# controller.net
KiCad netlist of a schematic drawn in Altium Designer
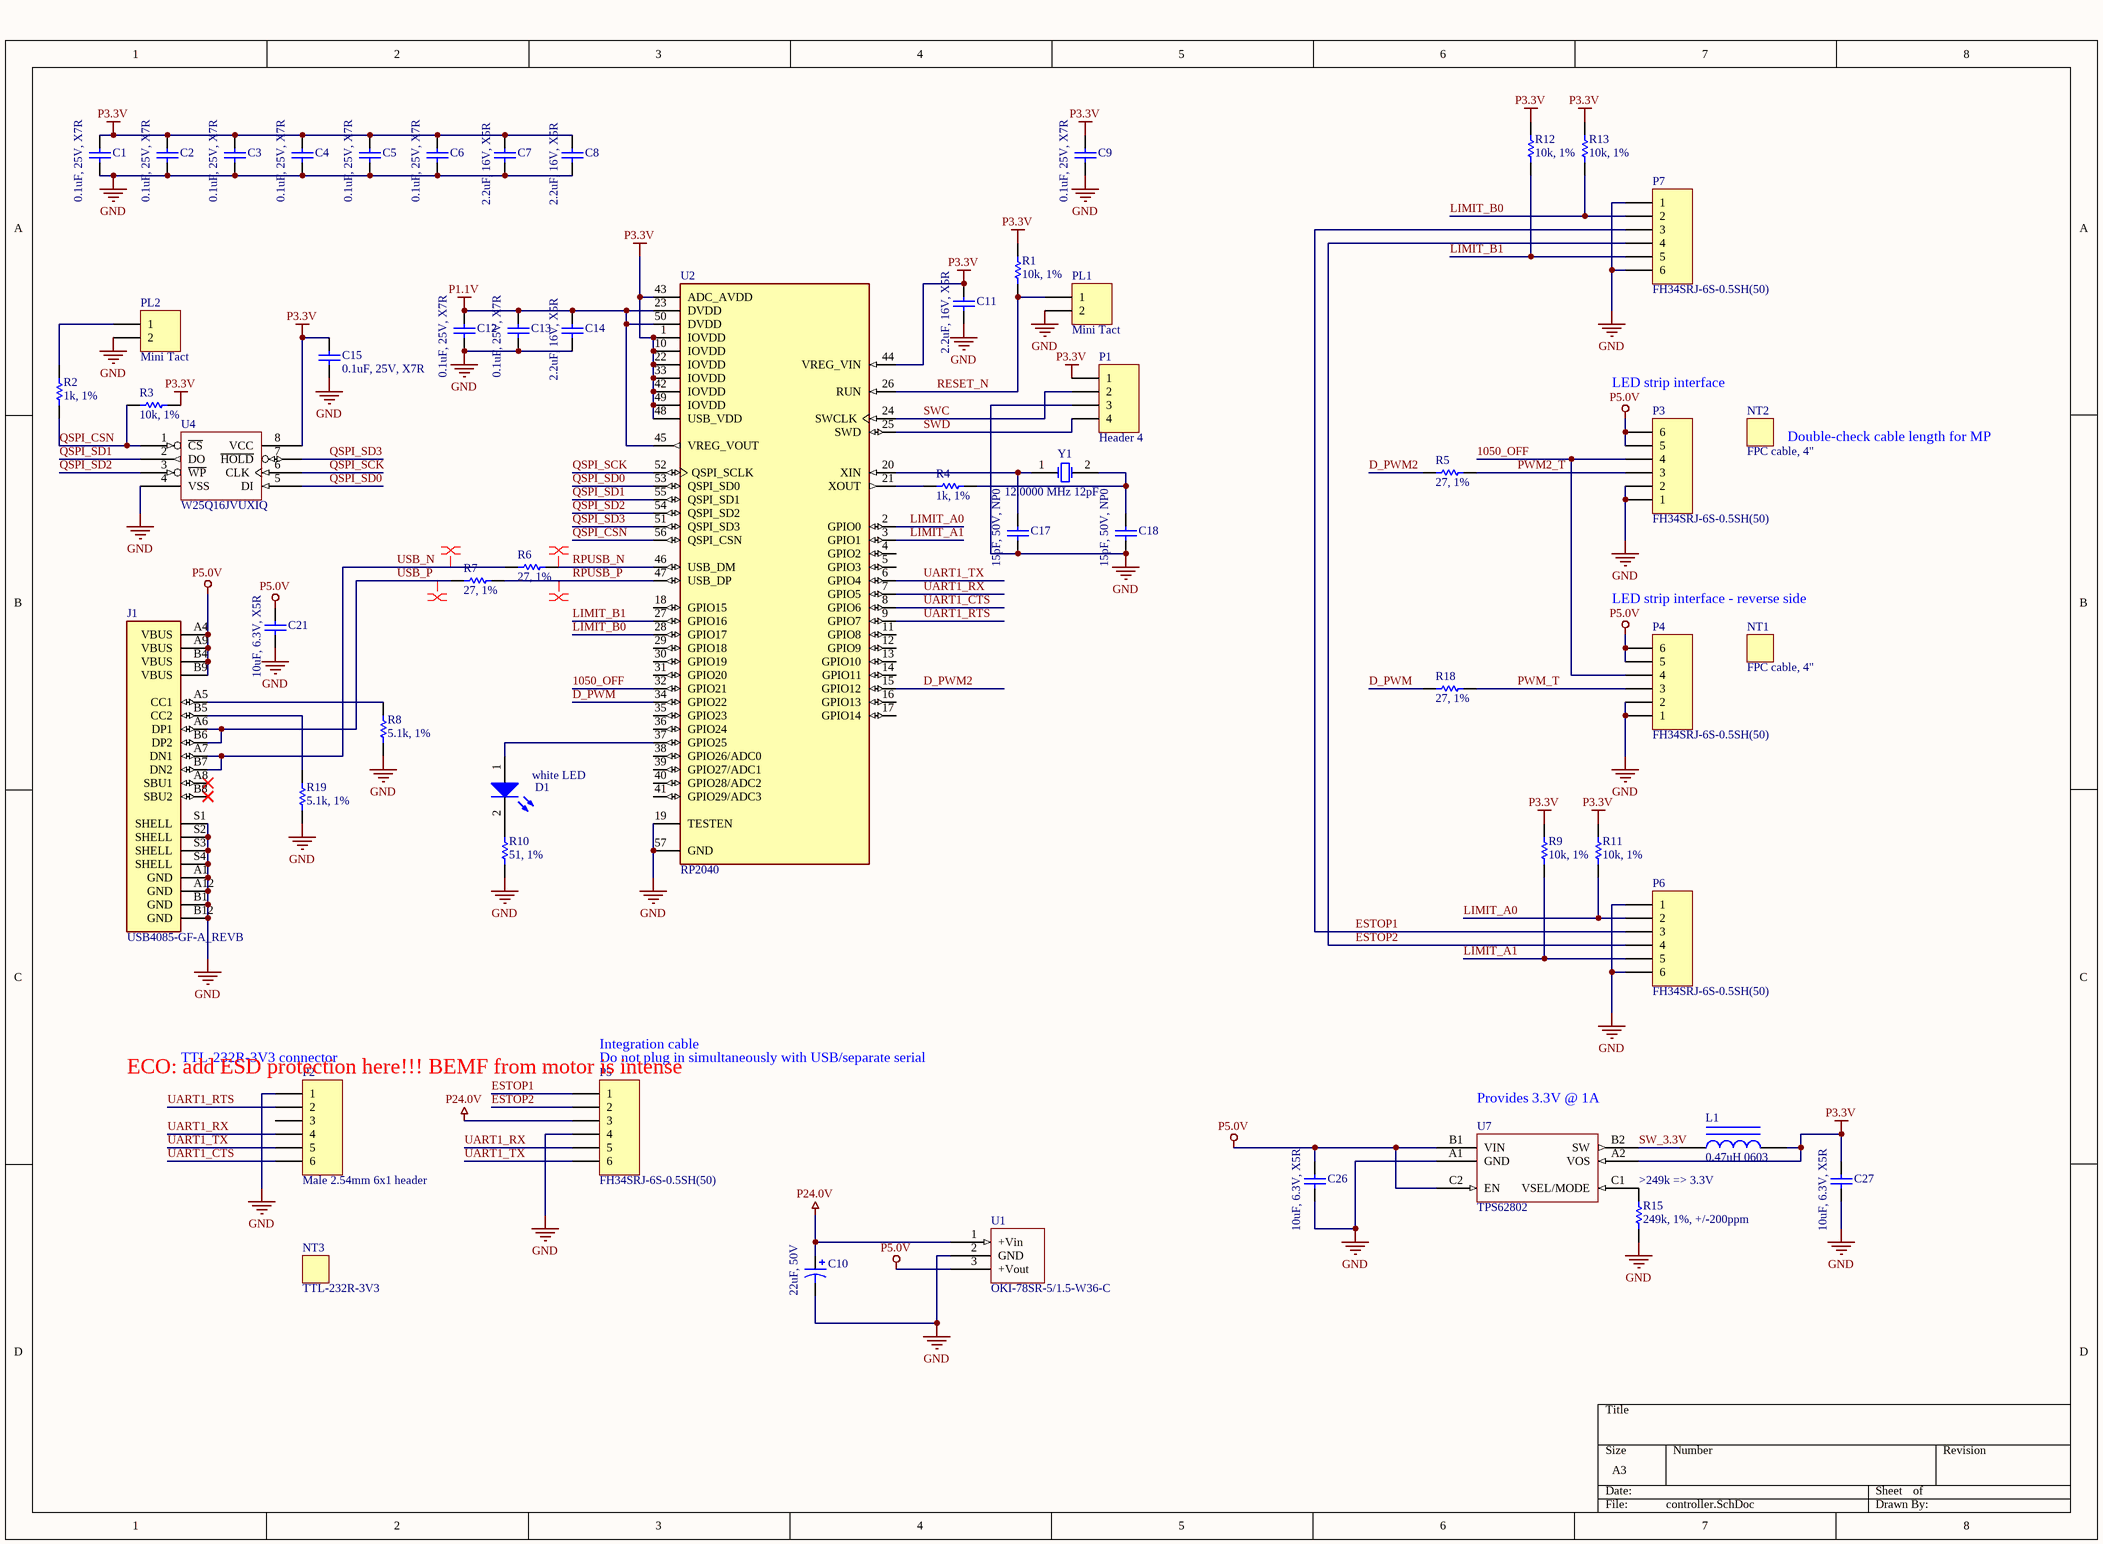
[diagram p0: controller.SchDoc]

(export (version "E")
  (design (tool "Eeschema 10.0.6"))
  (components
    (comp (ref "C1")
      (value "0.1uF, 25V, X7R")
      (footprint "B_CAP0603")
      (description "Capacitor (Semiconductor SIM Model)")
      (fields (field (name "MPN") "CC0603KRX7R8BB104"))
      (libsource (lib "Miscellaneous Devices") (part "Cap Semi"))
    )
    (comp (ref "C2")
      (value "0.1uF, 25V, X7R")
      (footprint "B_CAP0603")
      (description "Capacitor (Semiconductor SIM Model)")
      (fields (field (name "MPN") "CC0603KRX7R8BB104"))
      (libsource (lib "Miscellaneous Devices") (part "Cap Semi"))
    )
    (comp (ref "C3")
      (value "0.1uF, 25V, X7R")
      (footprint "B_CAP0603")
      (description "Capacitor (Semiconductor SIM Model)")
      (fields (field (name "MPN") "CC0603KRX7R8BB104"))
      (libsource (lib "Miscellaneous Devices") (part "Cap Semi"))
    )
    (comp (ref "C4")
      (value "0.1uF, 25V, X7R")
      (footprint "B_CAP0603")
      (description "Capacitor (Semiconductor SIM Model)")
      (fields (field (name "MPN") "CC0603KRX7R8BB104"))
      (libsource (lib "Miscellaneous Devices") (part "Cap Semi"))
    )
    (comp (ref "C5")
      (value "0.1uF, 25V, X7R")
      (footprint "B_CAP0603")
      (description "Capacitor (Semiconductor SIM Model)")
      (fields (field (name "MPN") "CC0603KRX7R8BB104"))
      (libsource (lib "Miscellaneous Devices") (part "Cap Semi"))
    )
    (comp (ref "C6")
      (value "0.1uF, 25V, X7R")
      (footprint "B_CAP0603")
      (description "Capacitor (Semiconductor SIM Model)")
      (fields (field (name "MPN") "CC0603KRX7R8BB104"))
      (libsource (lib "Miscellaneous Devices") (part "Cap Semi"))
    )
    (comp (ref "C7")
      (value "2.2uF, 16V, X5R")
      (footprint "B_CAP0603")
      (description "Capacitor (Semiconductor SIM Model)")
      (fields (field (name "MPN") "CL10A225KO8NNNC"))
      (libsource (lib "Miscellaneous Devices") (part "Cap Semi"))
    )
    (comp (ref "C8")
      (value "2.2uF, 16V, X5R")
      (footprint "B_CAP0603")
      (description "Capacitor (Semiconductor SIM Model)")
      (fields (field (name "MPN") "CL10A225KO8NNNC"))
      (libsource (lib "Miscellaneous Devices") (part "Cap Semi"))
    )
    (comp (ref "C9")
      (value "0.1uF, 25V, X7R")
      (footprint "B_CAP0603")
      (description "Capacitor (Semiconductor SIM Model)")
      (fields (field (name "MPN") "CC0603KRX7R8BB104"))
      (libsource (lib "Miscellaneous Devices") (part "Cap Semi"))
    )
    (comp (ref "C10")
      (value "22uF, 50V")
      (footprint "CAPAE7066X61N")
      (description "Polarized Capacitor (Radial)")
      (fields (field (name "MPN") "EEH-ZA1H220P"))
      (libsource (lib "Miscellaneous Devices") (part "Cap Pol1"))
    )
    (comp (ref "C11")
      (value "2.2uF, 16V, X5R")
      (footprint "B_CAP0603")
      (description "Capacitor (Semiconductor SIM Model)")
      (fields (field (name "MPN") "CL10A225KO8NNNC"))
      (libsource (lib "Miscellaneous Devices") (part "Cap Semi"))
    )
    (comp (ref "C12")
      (value "0.1uF, 25V, X7R")
      (footprint "B_CAP0603")
      (description "Capacitor (Semiconductor SIM Model)")
      (fields (field (name "MPN") "CC0603KRX7R8BB104"))
      (libsource (lib "Miscellaneous Devices") (part "Cap Semi"))
    )
    (comp (ref "C13")
      (value "0.1uF, 25V, X7R")
      (footprint "B_CAP0603")
      (description "Capacitor (Semiconductor SIM Model)")
      (fields (field (name "MPN") "CC0603KRX7R8BB104"))
      (libsource (lib "Miscellaneous Devices") (part "Cap Semi"))
    )
    (comp (ref "C14")
      (value "2.2uF, 16V, X5R")
      (footprint "B_CAP0603")
      (description "Capacitor (Semiconductor SIM Model)")
      (fields (field (name "MPN") "CL10A225KO8NNNC"))
      (libsource (lib "Miscellaneous Devices") (part "Cap Semi"))
    )
    (comp (ref "C15")
      (value "0.1uF, 25V, X7R")
      (footprint "B_CAP0603")
      (description "Capacitor (Semiconductor SIM Model)")
      (fields (field (name "MPN") "CC0603KRX7R8BB104"))
      (libsource (lib "Miscellaneous Devices") (part "Cap Semi"))
    )
    (comp (ref "C17")
      (value "15pF, 50V, NP0")
      (footprint "B_CAP0603")
      (description "Capacitor (Semiconductor SIM Model)")
      (fields (field (name "MPN") "CL10C150JB81PNC"))
      (libsource (lib "Miscellaneous Devices") (part "Cap Semi"))
    )
    (comp (ref "C18")
      (value "15pF, 50V, NP0")
      (footprint "B_CAP0603")
      (description "Capacitor (Semiconductor SIM Model)")
      (fields (field (name "MPN") "CL10C150JB81PNC"))
      (libsource (lib "Miscellaneous Devices") (part "Cap Semi"))
    )
    (comp (ref "C21")
      (value "10uF, 6.3V, X5R")
      (footprint "B_CAP0603")
      (description "Capacitor (Semiconductor SIM Model)")
      (fields (field (name "MPN") "CL10A106MQ8NNNC"))
      (libsource (lib "Miscellaneous Devices") (part "Cap Semi"))
    )
    (comp (ref "C26")
      (value "10uF, 6.3V, X5R")
      (footprint "B_CAP0603")
      (description "Capacitor (Semiconductor SIM Model)")
      (fields (field (name "MPN") "CL10A106MQ8NNNC"))
      (libsource (lib "Miscellaneous Devices") (part "Cap Semi"))
    )
    (comp (ref "C27")
      (value "10uF, 6.3V, X5R")
      (footprint "B_CAP0603")
      (description "Capacitor (Semiconductor SIM Model)")
      (fields (field (name "MPN") "CL10A106MQ8NNNC"))
      (libsource (lib "Miscellaneous Devices") (part "Cap Semi"))
    )
    (comp (ref "D1")
      (value "white LED")
      (footprint "B_LED0805")
      (description "Typical RED, GREEN, YELLOW, AMBER GaAs LED")
      (fields (field (name "MPN") "EAST2012WA1"))
      (libsource (lib "Miscellaneous Devices") (part "LED2"))
    )
    (comp (ref "J1")
      (value "USB4085-GF-A_REVB")
      (footprint "GCT_USB4085-GF-A_REVB")
      (fields (field (name "MF") "Global Connector Technology") (field (name "MP") "USB4085-GF-A"))
      (libsource (lib "USB4085-GF-A_REVB") (part "USB4085-GF-A_REVB"))
    )
    (comp (ref "L1")
      (value "0.47uH 0603")
      (footprint "B_IND0603")
      (description "Magnetic-Core Inductor")
      (fields (field (name "MPN") "TFM160808ALC-R47MTAA"))
      (libsource (lib "Miscellaneous Devices") (part "Inductor Iron"))
    )
    (comp (ref "NT1")
      (value "FPC cable, 4\"")
      (description "Placeholder for non-board BOM items")
      (fields (field (name "MPN") "AFFC-050-06-102-11"))
      (libsource (lib "commonsch") (part "NOTE"))
    )
    (comp (ref "NT2")
      (value "FPC cable, 4\"")
      (description "Placeholder for non-board BOM items")
      (fields (field (name "MPN") "AFFC-050-06-102-11"))
      (libsource (lib "commonsch") (part "NOTE"))
    )
    (comp (ref "NT3")
      (value "TTL-232R-3V3")
      (description "Placeholder for non-board BOM items")
      (libsource (lib "commonsch") (part "NOTE"))
    )
    (comp (ref "P1")
      (value "Header 4")
      (footprint "HDR1X4")
      (description "Header, 4-Pin")
      (fields (field (name "MPN") "PH1-04-UA / ANY") (field (name "PUBLISHER") "Altium Limited"))
      (libsource (lib "Miscellaneous Connectors") (part "Header 4"))
    )
    (comp (ref "P2")
      (value "Male 2.54mm 6x1 header")
      (footprint "HDR1X6")
      (description "Header, 6-Pin")
      (fields (field (name "MPN") "PH1-06-UA / ANY") (field (name "PUBLISHER") "Altium Limited"))
      (libsource (lib "") (part "Header 6_1"))
    )
    (comp (ref "P3")
      (value "FH34SRJ-6S-0.5SH(50)")
      (footprint "HRS_FH34SRJ-6S-0.5SH(50)")
      (description "Header, 6-Pin")
      (fields (field (name "PUBLISHER") "Altium Limited"))
      (libsource (lib "Miscellaneous Connectors") (part "Header 6"))
    )
    (comp (ref "P4")
      (value "FH34SRJ-6S-0.5SH(50)")
      (footprint "HRS_FH34SRJ-6S-0.5SH(50)")
      (description "Header, 6-Pin")
      (fields (field (name "PUBLISHER") "Altium Limited"))
      (libsource (lib "Miscellaneous Connectors") (part "Header 6"))
    )
    (comp (ref "P5")
      (value "FH34SRJ-6S-0.5SH(50)")
      (footprint "HRS_FH34SRJ-6S-0.5SH(50)")
      (description "Header, 6-Pin")
      (fields (field (name "PUBLISHER") "Altium Limited"))
      (libsource (lib "") (part "Header 6_1"))
    )
    (comp (ref "P6")
      (value "FH34SRJ-6S-0.5SH(50)")
      (footprint "HRS_FH34SRJ-6S-0.5SH(50)")
      (description "Header, 6-Pin")
      (fields (field (name "PUBLISHER") "Altium Limited"))
      (libsource (lib "") (part "Header 6_1"))
    )
    (comp (ref "P7")
      (value "FH34SRJ-6S-0.5SH(50)")
      (footprint "HRS_FH34SRJ-6S-0.5SH(50)")
      (description "Header, 6-Pin")
      (fields (field (name "PUBLISHER") "Altium Limited"))
      (libsource (lib "") (part "Header 6_1"))
    )
    (comp (ref "PL1")
      (value "Mini Tact")
      (footprint "OMRON_B3U-1000P")
      (description "Header, 2-Pin")
      (fields (field (name "MPN") "B3U-1000P") (field (name "PUBLISHER") "Altium Limited"))
      (libsource (lib "Miscellaneous Connectors") (part "Header 2"))
    )
    (comp (ref "PL2")
      (value "Mini Tact")
      (footprint "OMRON_B3U-1000P")
      (description "Header, 2-Pin")
      (fields (field (name "MPN") "B3U-1000P") (field (name "PUBLISHER") "Altium Limited"))
      (libsource (lib "Miscellaneous Connectors") (part "Header 2"))
    )
    (comp (ref "R1")
      (value "10k, 1%")
      (footprint "B_RES0603")
      (description "Resistor")
      (fields (field (name "MPN") "RC0603FR-0710KL"))
      (libsource (lib "Miscellaneous Devices") (part "Res1"))
    )
    (comp (ref "R2")
      (value "1k, 1%")
      (footprint "B_RES0603")
      (description "Resistor")
      (fields (field (name "MPN") "ANY"))
      (libsource (lib "Miscellaneous Devices") (part "Res1"))
    )
    (comp (ref "R3")
      (value "10k, 1%")
      (footprint "B_RES0603")
      (description "Resistor")
      (fields (field (name "MPN") "RC0603FR-0710KL"))
      (libsource (lib "Miscellaneous Devices") (part "Res1"))
    )
    (comp (ref "R4")
      (value "1k, 1%")
      (footprint "B_RES0603")
      (description "Resistor")
      (fields (field (name "MPN") "ANY"))
      (libsource (lib "Miscellaneous Devices") (part "Res1"))
    )
    (comp (ref "R5")
      (value "27, 1%")
      (footprint "B_RES0603")
      (description "Resistor")
      (fields (field (name "MPN") "ANY"))
      (libsource (lib "Miscellaneous Devices") (part "Res1"))
    )
    (comp (ref "R6")
      (value "27, 1%")
      (footprint "B_RES0603")
      (description "Resistor")
      (fields (field (name "MPN") "ANY"))
      (libsource (lib "Miscellaneous Devices") (part "Res1"))
    )
    (comp (ref "R7")
      (value "27, 1%")
      (footprint "B_RES0603")
      (description "Resistor")
      (fields (field (name "MPN") "ANY"))
      (libsource (lib "Miscellaneous Devices") (part "Res1"))
    )
    (comp (ref "R8")
      (value "5.1k, 1%")
      (footprint "B_RES0603")
      (description "Resistor")
      (fields (field (name "MPN") "RC0603FR-075K1L"))
      (libsource (lib "Miscellaneous Devices") (part "Res1"))
    )
    (comp (ref "R9")
      (value "10k, 1%")
      (footprint "B_RES0603")
      (description "Resistor")
      (fields (field (name "MPN") "RC0603FR-0710KL"))
      (libsource (lib "Miscellaneous Devices") (part "Res1"))
    )
    (comp (ref "R10")
      (value "51, 1%")
      (footprint "B_RES0603")
      (description "Resistor")
      (fields (field (name "MPN") "ANY"))
      (libsource (lib "Miscellaneous Devices") (part "Res1"))
    )
    (comp (ref "R11")
      (value "10k, 1%")
      (footprint "B_RES0603")
      (description "Resistor")
      (fields (field (name "MPN") "RC0603FR-0710KL"))
      (libsource (lib "Miscellaneous Devices") (part "Res1"))
    )
    (comp (ref "R12")
      (value "10k, 1%")
      (footprint "B_RES0603")
      (description "Resistor")
      (fields (field (name "MPN") "RC0603FR-0710KL"))
      (libsource (lib "Miscellaneous Devices") (part "Res1"))
    )
    (comp (ref "R13")
      (value "10k, 1%")
      (footprint "B_RES0603")
      (description "Resistor")
      (fields (field (name "MPN") "RC0603FR-0710KL"))
      (libsource (lib "Miscellaneous Devices") (part "Res1"))
    )
    (comp (ref "R15")
      (value "249k, 1%, +/-200ppm")
      (footprint "B_RES0402")
      (description "Resistor")
      (fields (field (name "MPN") "RC0402FR-07249KL"))
      (libsource (lib "Miscellaneous Devices") (part "Res1"))
    )
    (comp (ref "R18")
      (value "27, 1%")
      (footprint "B_RES0603")
      (description "Resistor")
      (fields (field (name "MPN") "ANY"))
      (libsource (lib "Miscellaneous Devices") (part "Res1"))
    )
    (comp (ref "R19")
      (value "5.1k, 1%")
      (footprint "B_RES0603")
      (description "Resistor")
      (fields (field (name "MPN") "RC0603FR-075K1L"))
      (libsource (lib "Miscellaneous Devices") (part "Res1"))
    )
    (comp (ref "U1")
      (value "OKI-78SR-5/1.5-W36-C")
      (footprint "MURATA_OKI-78SR")
      (description "OKI-78SR switching regulator")
      (fields (field (name "MFG") "Murata"))
      (libsource (lib "commonsch-new") (part "VR20"))
    )
    (comp (ref "U2")
      (value "RP2040")
      (footprint "QFN40P700X700X90-57N")
      (description "RP2040 chip for Raspberry Pi Pico - ARMÂ® CortexÂ®-M0+ MCU 32-Bit")
      (fields (field (name "MF") "Raspberry Pi") (field (name "MPN") "SC0914(7/13)"))
      (libsource (lib "RP2040") (part "RP2040"))
    )
    (comp (ref "U4")
      (value "W25Q16JVUXIQ")
      (footprint "USON-8")
      (description "16Mbit SPI NOR FLASH")
      (libsource (lib "commonsch") (part "EN25P05-50GCP"))
    )
    (comp (ref "U7")
      (value "TPS62802")
      (footprint "BGA6C35P2X3_70X105X40_NSMD")
      (description "Buck regulator, 4MHz, 0.6A, 1.8V-3.3V, low Iq")
      (fields (field (name "MPN") "TPS62802YKAR"))
      (libsource (lib "altium-import") (part "root_0_TPS62802_"))
    )
    (comp (ref "Y1")
      (value "12.0000 MHz 12pF")
      (footprint "NDK_NX5032A")
      (description "Crystal Oscillator")
      (fields (field (name "MPN") "ECS-120-12-30-JGN-TR") (field (name "PUBLISHER") "Altium Limited"))
      (libsource (lib "Miscellaneous Devices") (part "XTAL"))
    )
  )
  (nets
    (net (code "1") (name "/1050_OFF") (class "Default")
      (node (ref "P3") (pin "4") (pinfunction "4_4") (pintype "passive"))
      (node (ref "P4") (pin "4") (pinfunction "4_4") (pintype "passive"))
      (node (ref "U2") (pin "32") (pinfunction "GPIO21_32") (pintype "bidirectional"))
    )
    (net (code "2") (name "/D_PWM") (class "Default")
      (node (ref "R18") (pin "1") (pinfunction "1_1") (pintype "passive"))
      (node (ref "U2") (pin "34") (pinfunction "GPIO22_34") (pintype "bidirectional"))
    )
    (net (code "3") (name "/D_PWM2") (class "Default")
      (node (ref "R5") (pin "1") (pinfunction "1_1") (pintype "passive"))
      (node (ref "U2") (pin "15") (pinfunction "GPIO12_15") (pintype "bidirectional"))
    )
    (net (code "4") (name "/ESTOP1") (class "Default")
      (node (ref "P5") (pin "1") (pinfunction "1_1") (pintype "passive"))
      (node (ref "P6") (pin "3") (pinfunction "3_3") (pintype "passive"))
      (node (ref "P7") (pin "3") (pinfunction "3_3") (pintype "passive"))
    )
    (net (code "5") (name "/ESTOP2") (class "Default")
      (node (ref "P5") (pin "2") (pinfunction "2_2") (pintype "passive"))
      (node (ref "P6") (pin "4") (pinfunction "4_4") (pintype "passive"))
      (node (ref "P7") (pin "4") (pinfunction "4_4") (pintype "passive"))
    )
    (net (code "6") (name "/LIMIT_A0") (class "Default")
      (node (ref "P6") (pin "2") (pinfunction "2_2") (pintype "passive"))
      (node (ref "R11") (pin "2") (pinfunction "2_2") (pintype "passive"))
      (node (ref "U2") (pin "2") (pinfunction "GPIO0_2") (pintype "bidirectional"))
    )
    (net (code "7") (name "/LIMIT_A1") (class "Default")
      (node (ref "P6") (pin "5") (pinfunction "5_5") (pintype "passive"))
      (node (ref "R9") (pin "2") (pinfunction "2_2") (pintype "passive"))
      (node (ref "U2") (pin "3") (pinfunction "GPIO1_3") (pintype "bidirectional"))
    )
    (net (code "8") (name "/LIMIT_B0") (class "Default")
      (node (ref "P7") (pin "2") (pinfunction "2_2") (pintype "passive"))
      (node (ref "R13") (pin "2") (pinfunction "2_2") (pintype "passive"))
      (node (ref "U2") (pin "28") (pinfunction "GPIO17_28") (pintype "bidirectional"))
    )
    (net (code "9") (name "/LIMIT_B1") (class "Default")
      (node (ref "P7") (pin "5") (pinfunction "5_5") (pintype "passive"))
      (node (ref "R12") (pin "2") (pinfunction "2_2") (pintype "passive"))
      (node (ref "U2") (pin "27") (pinfunction "GPIO16_27") (pintype "bidirectional"))
    )
    (net (code "10") (name "/PWM2_T") (class "Default")
      (node (ref "P3") (pin "3") (pinfunction "3_3") (pintype "passive"))
      (node (ref "R5") (pin "2") (pinfunction "2_2") (pintype "passive"))
    )
    (net (code "11") (name "/PWM_T") (class "Default")
      (node (ref "P4") (pin "3") (pinfunction "3_3") (pintype "passive"))
      (node (ref "R18") (pin "2") (pinfunction "2_2") (pintype "passive"))
    )
    (net (code "12") (name "/QSPI_CSN") (class "Default")
      (node (ref "R2") (pin "1") (pinfunction "1_1") (pintype "passive"))
      (node (ref "R3") (pin "1") (pinfunction "1_1") (pintype "passive"))
      (node (ref "U2") (pin "56") (pinfunction "QSPI_CSN_56") (pintype "bidirectional"))
      (node (ref "U4") (pin "1") (pinfunction "~{CS}_1") (pintype "input"))
    )
    (net (code "13") (name "/QSPI_SCK") (class "Default")
      (node (ref "U2") (pin "52") (pinfunction "QSPI_SCLK_52") (pintype "bidirectional"))
      (node (ref "U4") (pin "6") (pinfunction "CLK_6") (pintype "input"))
    )
    (net (code "14") (name "/QSPI_SD0") (class "Default")
      (node (ref "U2") (pin "53") (pinfunction "QSPI_SD0_53") (pintype "bidirectional"))
      (node (ref "U4") (pin "5") (pinfunction "DI_5") (pintype "input"))
    )
    (net (code "15") (name "/QSPI_SD1") (class "Default")
      (node (ref "U2") (pin "55") (pinfunction "QSPI_SD1_55") (pintype "bidirectional"))
      (node (ref "U4") (pin "2") (pinfunction "DO_2") (pintype "output"))
    )
    (net (code "16") (name "/QSPI_SD2") (class "Default")
      (node (ref "U2") (pin "54") (pinfunction "QSPI_SD2_54") (pintype "bidirectional"))
      (node (ref "U4") (pin "3") (pinfunction "~{WP}_3") (pintype "input"))
    )
    (net (code "17") (name "/QSPI_SD3") (class "Default")
      (node (ref "U2") (pin "51") (pinfunction "QSPI_SD3_51") (pintype "bidirectional"))
      (node (ref "U4") (pin "7") (pinfunction "~{HOLD}_7") (pintype "bidirectional"))
    )
    (net (code "18") (name "/RESET_N") (class "Default")
      (node (ref "PL1") (pin "1") (pinfunction "1_1") (pintype "passive"))
      (node (ref "R1") (pin "2") (pinfunction "2_2") (pintype "passive"))
      (node (ref "U2") (pin "26") (pinfunction "RUN_26") (pintype "input"))
    )
    (net (code "19") (name "/RPUSB_N") (class "Default")
      (node (ref "R6") (pin "2") (pinfunction "2_2") (pintype "passive"))
      (node (ref "U2") (pin "46") (pinfunction "USB_DM_46") (pintype "bidirectional"))
    )
    (net (code "20") (name "/RPUSB_P") (class "Default")
      (node (ref "R7") (pin "2") (pinfunction "2_2") (pintype "passive"))
      (node (ref "U2") (pin "47") (pinfunction "USB_DP_47") (pintype "bidirectional"))
    )
    (net (code "21") (name "/SWC") (class "Default")
      (node (ref "P1") (pin "2") (pinfunction "2_2") (pintype "passive"))
      (node (ref "U2") (pin "24") (pinfunction "SWCLK_24") (pintype "input"))
    )
    (net (code "22") (name "/SWD") (class "Default")
      (node (ref "P1") (pin "4") (pinfunction "4_4") (pintype "passive"))
      (node (ref "U2") (pin "25") (pinfunction "SWD_25") (pintype "bidirectional"))
    )
    (net (code "23") (name "/SW_3.3V") (class "Default")
      (node (ref "L1") (pin "1") (pinfunction "1_1") (pintype "passive"))
      (node (ref "U7") (pin "B2") (pinfunction "SW_B2") (pintype "output"))
    )
    (net (code "24") (name "/UART1_CTS") (class "Default")
      (node (ref "P2") (pin "6") (pinfunction "6_6") (pintype "passive"))
      (node (ref "U2") (pin "8") (pinfunction "GPIO6_8") (pintype "bidirectional"))
    )
    (net (code "25") (name "/UART1_RTS") (class "Default")
      (node (ref "P2") (pin "2") (pinfunction "2_2") (pintype "passive"))
      (node (ref "U2") (pin "9") (pinfunction "GPIO7_9") (pintype "bidirectional"))
    )
    (net (code "26") (name "/UART1_RX") (class "Default")
      (node (ref "P2") (pin "4") (pinfunction "4_4") (pintype "passive"))
      (node (ref "P5") (pin "5") (pinfunction "5_5") (pintype "passive"))
      (node (ref "U2") (pin "7") (pinfunction "GPIO5_7") (pintype "bidirectional"))
    )
    (net (code "27") (name "/UART1_TX") (class "Default")
      (node (ref "P2") (pin "5") (pinfunction "5_5") (pintype "passive"))
      (node (ref "P5") (pin "6") (pinfunction "6_6") (pintype "passive"))
      (node (ref "U2") (pin "6") (pinfunction "GPIO4_6") (pintype "bidirectional"))
    )
    (net (code "28") (name "/USB_N") (class "Default")
      (node (ref "J1") (pin "A7") (pinfunction "DN1_A7") (pintype "bidirectional"))
      (node (ref "J1") (pin "B7") (pinfunction "DN2_B7") (pintype "bidirectional"))
      (node (ref "R6") (pin "1") (pinfunction "1_1") (pintype "passive"))
    )
    (net (code "29") (name "/USB_P") (class "Default")
      (node (ref "J1") (pin "A6") (pinfunction "DP1_A6") (pintype "bidirectional"))
      (node (ref "J1") (pin "B6") (pinfunction "DP2_B6") (pintype "bidirectional"))
      (node (ref "R7") (pin "1") (pinfunction "1_1") (pintype "passive"))
    )
    (net (code "30") (name "GND") (class "Default")
      (node (ref "C1") (pin "2") (pinfunction "2_2") (pintype "passive"))
      (node (ref "C10") (pin "2") (pinfunction "2_2") (pintype "passive"))
      (node (ref "C11") (pin "2") (pinfunction "2_2") (pintype "passive"))
      (node (ref "C12") (pin "2") (pinfunction "2_2") (pintype "passive"))
      (node (ref "C13") (pin "2") (pinfunction "2_2") (pintype "passive"))
      (node (ref "C14") (pin "2") (pinfunction "2_2") (pintype "passive"))
      (node (ref "C15") (pin "1") (pinfunction "1_1") (pintype "passive"))
      (node (ref "C17") (pin "1") (pinfunction "1_1") (pintype "passive"))
      (node (ref "C18") (pin "1") (pinfunction "1_1") (pintype "passive"))
      (node (ref "C2") (pin "2") (pinfunction "2_2") (pintype "passive"))
      (node (ref "C21") (pin "2") (pinfunction "2_2") (pintype "passive"))
      (node (ref "C26") (pin "2") (pinfunction "2_2") (pintype "passive"))
      (node (ref "C27") (pin "2") (pinfunction "2_2") (pintype "passive"))
      (node (ref "C3") (pin "2") (pinfunction "2_2") (pintype "passive"))
      (node (ref "C4") (pin "2") (pinfunction "2_2") (pintype "passive"))
      (node (ref "C5") (pin "2") (pinfunction "2_2") (pintype "passive"))
      (node (ref "C6") (pin "2") (pinfunction "2_2") (pintype "passive"))
      (node (ref "C7") (pin "2") (pinfunction "2_2") (pintype "passive"))
      (node (ref "C8") (pin "2") (pinfunction "2_2") (pintype "passive"))
      (node (ref "C9") (pin "2") (pinfunction "2_2") (pintype "passive"))
      (node (ref "J1") (pin "A1") (pinfunction "GND_A1") (pintype "power_in"))
      (node (ref "J1") (pin "A12") (pinfunction "GND_A12") (pintype "power_in"))
      (node (ref "J1") (pin "B1") (pinfunction "GND_B1") (pintype "power_in"))
      (node (ref "J1") (pin "B12") (pinfunction "GND_B12") (pintype "power_in"))
      (node (ref "J1") (pin "S1") (pinfunction "SHELL_S1") (pintype "passive"))
      (node (ref "J1") (pin "S2") (pinfunction "SHELL_S2") (pintype "passive"))
      (node (ref "J1") (pin "S3") (pinfunction "SHELL_S3") (pintype "passive"))
      (node (ref "J1") (pin "S4") (pinfunction "SHELL_S4") (pintype "passive"))
      (node (ref "P1") (pin "3") (pinfunction "3_3") (pintype "passive"))
      (node (ref "P2") (pin "1") (pinfunction "1_1") (pintype "passive"))
      (node (ref "P3") (pin "1") (pinfunction "1_1") (pintype "passive"))
      (node (ref "P3") (pin "2") (pinfunction "2_2") (pintype "passive"))
      (node (ref "P4") (pin "1") (pinfunction "1_1") (pintype "passive"))
      (node (ref "P4") (pin "2") (pinfunction "2_2") (pintype "passive"))
      (node (ref "P5") (pin "4") (pinfunction "4_4") (pintype "passive"))
      (node (ref "P6") (pin "1") (pinfunction "1_1") (pintype "passive"))
      (node (ref "P6") (pin "6") (pinfunction "6_6") (pintype "passive"))
      (node (ref "P7") (pin "1") (pinfunction "1_1") (pintype "passive"))
      (node (ref "P7") (pin "6") (pinfunction "6_6") (pintype "passive"))
      (node (ref "PL1") (pin "2") (pinfunction "2_2") (pintype "passive"))
      (node (ref "PL2") (pin "2") (pinfunction "2_2") (pintype "passive"))
      (node (ref "R10") (pin "1") (pinfunction "1_1") (pintype "passive"))
      (node (ref "R15") (pin "2") (pinfunction "2_2") (pintype "passive"))
      (node (ref "R19") (pin "1") (pinfunction "1_1") (pintype "passive"))
      (node (ref "R8") (pin "1") (pinfunction "1_1") (pintype "passive"))
      (node (ref "U1") (pin "2") (pinfunction "GND_2") (pintype "power_in"))
      (node (ref "U2") (pin "19") (pinfunction "TESTEN_19") (pintype "passive"))
      (node (ref "U2") (pin "57") (pinfunction "GND_57") (pintype "power_in"))
      (node (ref "U4") (pin "4") (pinfunction "VSS_4") (pintype "power_in"))
      (node (ref "U7") (pin "A1") (pinfunction "GND_A1") (pintype "power_in"))
    )
    (net (code "31") (name "Net-(D1-A)") (class "Default")
      (node (ref "D1") (pin "1") (pinfunction "A_1") (pintype "passive"))
      (node (ref "U2") (pin "37") (pinfunction "GPIO25_37") (pintype "bidirectional"))
    )
    (net (code "32") (name "Net-(D1-K)") (class "Default")
      (node (ref "D1") (pin "2") (pinfunction "K_2") (pintype "passive"))
      (node (ref "R10") (pin "2") (pinfunction "2_2") (pintype "passive"))
    )
    (net (code "33") (name "Net-(J1-CC1)") (class "Default")
      (node (ref "J1") (pin "A5") (pinfunction "CC1_A5") (pintype "bidirectional"))
      (node (ref "R8") (pin "2") (pinfunction "2_2") (pintype "passive"))
    )
    (net (code "34") (name "Net-(J1-CC2)") (class "Default")
      (node (ref "J1") (pin "B5") (pinfunction "CC2_B5") (pintype "bidirectional"))
      (node (ref "R19") (pin "2") (pinfunction "2_2") (pintype "passive"))
    )
    (net (code "35") (name "Net-(PL2-Pad1)") (class "Default")
      (node (ref "PL2") (pin "1") (pinfunction "1_1") (pintype "passive"))
      (node (ref "R2") (pin "2") (pinfunction "2_2") (pintype "passive"))
    )
    (net (code "36") (name "Net-(U2-XIN)") (class "Default")
      (node (ref "C17") (pin "2") (pinfunction "2_2") (pintype "passive"))
      (node (ref "U2") (pin "20") (pinfunction "XIN_20") (pintype "input"))
      (node (ref "Y1") (pin "1") (pinfunction "OSC1_1") (pintype "passive"))
    )
    (net (code "37") (name "Net-(U2-XOUT)") (class "Default")
      (node (ref "R4") (pin "1") (pinfunction "1_1") (pintype "passive"))
      (node (ref "U2") (pin "21") (pinfunction "XOUT_21") (pintype "output"))
    )
    (net (code "38") (name "Net-(U7-VSEL{slash}MODE)") (class "Default")
      (node (ref "R15") (pin "1") (pinfunction "1_1") (pintype "passive"))
      (node (ref "U7") (pin "C1") (pinfunction "VSEL/MODE_C1") (pintype "input"))
    )
    (net (code "39") (name "Net-(Y1-OSC2)") (class "Default")
      (node (ref "C18") (pin "2") (pinfunction "2_2") (pintype "passive"))
      (node (ref "R4") (pin "2") (pinfunction "2_2") (pintype "passive"))
      (node (ref "Y1") (pin "2") (pinfunction "OSC2_2") (pintype "passive"))
    )
    (net (code "40") (name "P1.1V") (class "Default")
      (node (ref "C12") (pin "1") (pinfunction "1_1") (pintype "passive"))
      (node (ref "C13") (pin "1") (pinfunction "1_1") (pintype "passive"))
      (node (ref "C14") (pin "1") (pinfunction "1_1") (pintype "passive"))
      (node (ref "U2") (pin "23") (pinfunction "DVDD_23") (pintype "power_in"))
      (node (ref "U2") (pin "45") (pinfunction "VREG_VOUT_45") (pintype "output"))
      (node (ref "U2") (pin "50") (pinfunction "DVDD_50") (pintype "power_in"))
    )
    (net (code "41") (name "P3.3V") (class "Default")
      (node (ref "C1") (pin "1") (pinfunction "1_1") (pintype "passive"))
      (node (ref "C11") (pin "1") (pinfunction "1_1") (pintype "passive"))
      (node (ref "C15") (pin "2") (pinfunction "2_2") (pintype "passive"))
      (node (ref "C2") (pin "1") (pinfunction "1_1") (pintype "passive"))
      (node (ref "C27") (pin "1") (pinfunction "1_1") (pintype "passive"))
      (node (ref "C3") (pin "1") (pinfunction "1_1") (pintype "passive"))
      (node (ref "C4") (pin "1") (pinfunction "1_1") (pintype "passive"))
      (node (ref "C5") (pin "1") (pinfunction "1_1") (pintype "passive"))
      (node (ref "C6") (pin "1") (pinfunction "1_1") (pintype "passive"))
      (node (ref "C7") (pin "1") (pinfunction "1_1") (pintype "passive"))
      (node (ref "C8") (pin "1") (pinfunction "1_1") (pintype "passive"))
      (node (ref "C9") (pin "1") (pinfunction "1_1") (pintype "passive"))
      (node (ref "L1") (pin "2") (pinfunction "2_2") (pintype "passive"))
      (node (ref "P1") (pin "1") (pinfunction "1_1") (pintype "passive"))
      (node (ref "R1") (pin "1") (pinfunction "1_1") (pintype "passive"))
      (node (ref "R11") (pin "1") (pinfunction "1_1") (pintype "passive"))
      (node (ref "R12") (pin "1") (pinfunction "1_1") (pintype "passive"))
      (node (ref "R13") (pin "1") (pinfunction "1_1") (pintype "passive"))
      (node (ref "R3") (pin "2") (pinfunction "2_2") (pintype "passive"))
      (node (ref "R9") (pin "1") (pinfunction "1_1") (pintype "passive"))
      (node (ref "U2") (pin "1") (pinfunction "IOVDD_1") (pintype "power_in"))
      (node (ref "U2") (pin "10") (pinfunction "IOVDD_10") (pintype "power_in"))
      (node (ref "U2") (pin "22") (pinfunction "IOVDD_22") (pintype "power_in"))
      (node (ref "U2") (pin "33") (pinfunction "IOVDD_33") (pintype "power_in"))
      (node (ref "U2") (pin "42") (pinfunction "IOVDD_42") (pintype "power_in"))
      (node (ref "U2") (pin "43") (pinfunction "ADC_AVDD_43") (pintype "power_in"))
      (node (ref "U2") (pin "44") (pinfunction "VREG_VIN_44") (pintype "input"))
      (node (ref "U2") (pin "48") (pinfunction "USB_VDD_48") (pintype "power_in"))
      (node (ref "U2") (pin "49") (pinfunction "IOVDD_49") (pintype "power_in"))
      (node (ref "U4") (pin "8") (pinfunction "VCC_8") (pintype "power_in"))
      (node (ref "U7") (pin "A2") (pinfunction "VOS_A2") (pintype "input"))
    )
    (net (code "42") (name "P5.0V") (class "Default")
      (node (ref "C21") (pin "1") (pinfunction "1_1") (pintype "passive"))
      (node (ref "C26") (pin "1") (pinfunction "1_1") (pintype "passive"))
      (node (ref "J1") (pin "A4") (pinfunction "VBUS_A4") (pintype "power_in"))
      (node (ref "J1") (pin "A9") (pinfunction "VBUS_A9") (pintype "power_in"))
      (node (ref "J1") (pin "B4") (pinfunction "VBUS_B4") (pintype "power_in"))
      (node (ref "J1") (pin "B9") (pinfunction "VBUS_B9") (pintype "power_in"))
      (node (ref "P3") (pin "5") (pinfunction "5_5") (pintype "passive"))
      (node (ref "P3") (pin "6") (pinfunction "6_6") (pintype "passive"))
      (node (ref "P4") (pin "5") (pinfunction "5_5") (pintype "passive"))
      (node (ref "P4") (pin "6") (pinfunction "6_6") (pintype "passive"))
      (node (ref "U1") (pin "3") (pinfunction "+Vout_3") (pintype "power_in"))
      (node (ref "U7") (pin "B1") (pinfunction "VIN_B1") (pintype "power_in"))
      (node (ref "U7") (pin "C2") (pinfunction "EN_C2") (pintype "input"))
    )
    (net (code "43") (name "P24.0V") (class "Default")
      (node (ref "C10") (pin "1") (pinfunction "1_1") (pintype "passive"))
      (node (ref "P5") (pin "3") (pinfunction "3_3") (pintype "passive"))
      (node (ref "U1") (pin "1") (pinfunction "+Vin_1") (pintype "input"))
    )
    (net (code "44") (name "unconnected-(J1-SBU1-PadA8)") (class "Default")
      (node (ref "J1") (pin "A8") (pinfunction "SBU1_A8") (pintype "bidirectional+no_connect"))
    )
    (net (code "45") (name "unconnected-(J1-SBU2-PadB8)") (class "Default")
      (node (ref "J1") (pin "B8") (pinfunction "SBU2_B8") (pintype "bidirectional+no_connect"))
    )
    (net (code "46") (name "unconnected-(P2-Pad3)") (class "Default")
      (node (ref "P2") (pin "3") (pinfunction "3_3") (pintype "passive"))
    )
    (net (code "47") (name "unconnected-(U2-GPIO2-Pad4)") (class "Default")
      (node (ref "U2") (pin "4") (pinfunction "GPIO2_4") (pintype "bidirectional"))
    )
    (net (code "48") (name "unconnected-(U2-GPIO3-Pad5)") (class "Default")
      (node (ref "U2") (pin "5") (pinfunction "GPIO3_5") (pintype "bidirectional"))
    )
    (net (code "49") (name "unconnected-(U2-GPIO8-Pad11)") (class "Default")
      (node (ref "U2") (pin "11") (pinfunction "GPIO8_11") (pintype "bidirectional"))
    )
    (net (code "50") (name "unconnected-(U2-GPIO9-Pad12)") (class "Default")
      (node (ref "U2") (pin "12") (pinfunction "GPIO9_12") (pintype "bidirectional"))
    )
    (net (code "51") (name "unconnected-(U2-GPIO10-Pad13)") (class "Default")
      (node (ref "U2") (pin "13") (pinfunction "GPIO10_13") (pintype "bidirectional"))
    )
    (net (code "52") (name "unconnected-(U2-GPIO11-Pad14)") (class "Default")
      (node (ref "U2") (pin "14") (pinfunction "GPIO11_14") (pintype "bidirectional"))
    )
    (net (code "53") (name "unconnected-(U2-GPIO13-Pad16)") (class "Default")
      (node (ref "U2") (pin "16") (pinfunction "GPIO13_16") (pintype "bidirectional"))
    )
    (net (code "54") (name "unconnected-(U2-GPIO14-Pad17)") (class "Default")
      (node (ref "U2") (pin "17") (pinfunction "GPIO14_17") (pintype "bidirectional"))
    )
    (net (code "55") (name "unconnected-(U2-GPIO15-Pad18)") (class "Default")
      (node (ref "U2") (pin "18") (pinfunction "GPIO15_18") (pintype "bidirectional"))
    )
    (net (code "56") (name "unconnected-(U2-GPIO18-Pad29)") (class "Default")
      (node (ref "U2") (pin "29") (pinfunction "GPIO18_29") (pintype "bidirectional"))
    )
    (net (code "57") (name "unconnected-(U2-GPIO19-Pad30)") (class "Default")
      (node (ref "U2") (pin "30") (pinfunction "GPIO19_30") (pintype "bidirectional"))
    )
    (net (code "58") (name "unconnected-(U2-GPIO20-Pad31)") (class "Default")
      (node (ref "U2") (pin "31") (pinfunction "GPIO20_31") (pintype "bidirectional"))
    )
    (net (code "59") (name "unconnected-(U2-GPIO23-Pad35)") (class "Default")
      (node (ref "U2") (pin "35") (pinfunction "GPIO23_35") (pintype "bidirectional"))
    )
    (net (code "60") (name "unconnected-(U2-GPIO24-Pad36)") (class "Default")
      (node (ref "U2") (pin "36") (pinfunction "GPIO24_36") (pintype "bidirectional"))
    )
    (net (code "61") (name "unconnected-(U2-GPIO26{slash}ADC0-Pad38)") (class "Default")
      (node (ref "U2") (pin "38") (pinfunction "GPIO26/ADC0_38") (pintype "bidirectional"))
    )
    (net (code "62") (name "unconnected-(U2-GPIO27{slash}ADC1-Pad39)") (class "Default")
      (node (ref "U2") (pin "39") (pinfunction "GPIO27/ADC1_39") (pintype "bidirectional"))
    )
    (net (code "63") (name "unconnected-(U2-GPIO28{slash}ADC2-Pad40)") (class "Default")
      (node (ref "U2") (pin "40") (pinfunction "GPIO28/ADC2_40") (pintype "bidirectional"))
    )
    (net (code "64") (name "unconnected-(U2-GPIO29{slash}ADC3-Pad41)") (class "Default")
      (node (ref "U2") (pin "41") (pinfunction "GPIO29/ADC3_41") (pintype "bidirectional"))
    )
  )
)
